# WS2818B.net
KiCad netlist of a schematic drawn in Altium Designer
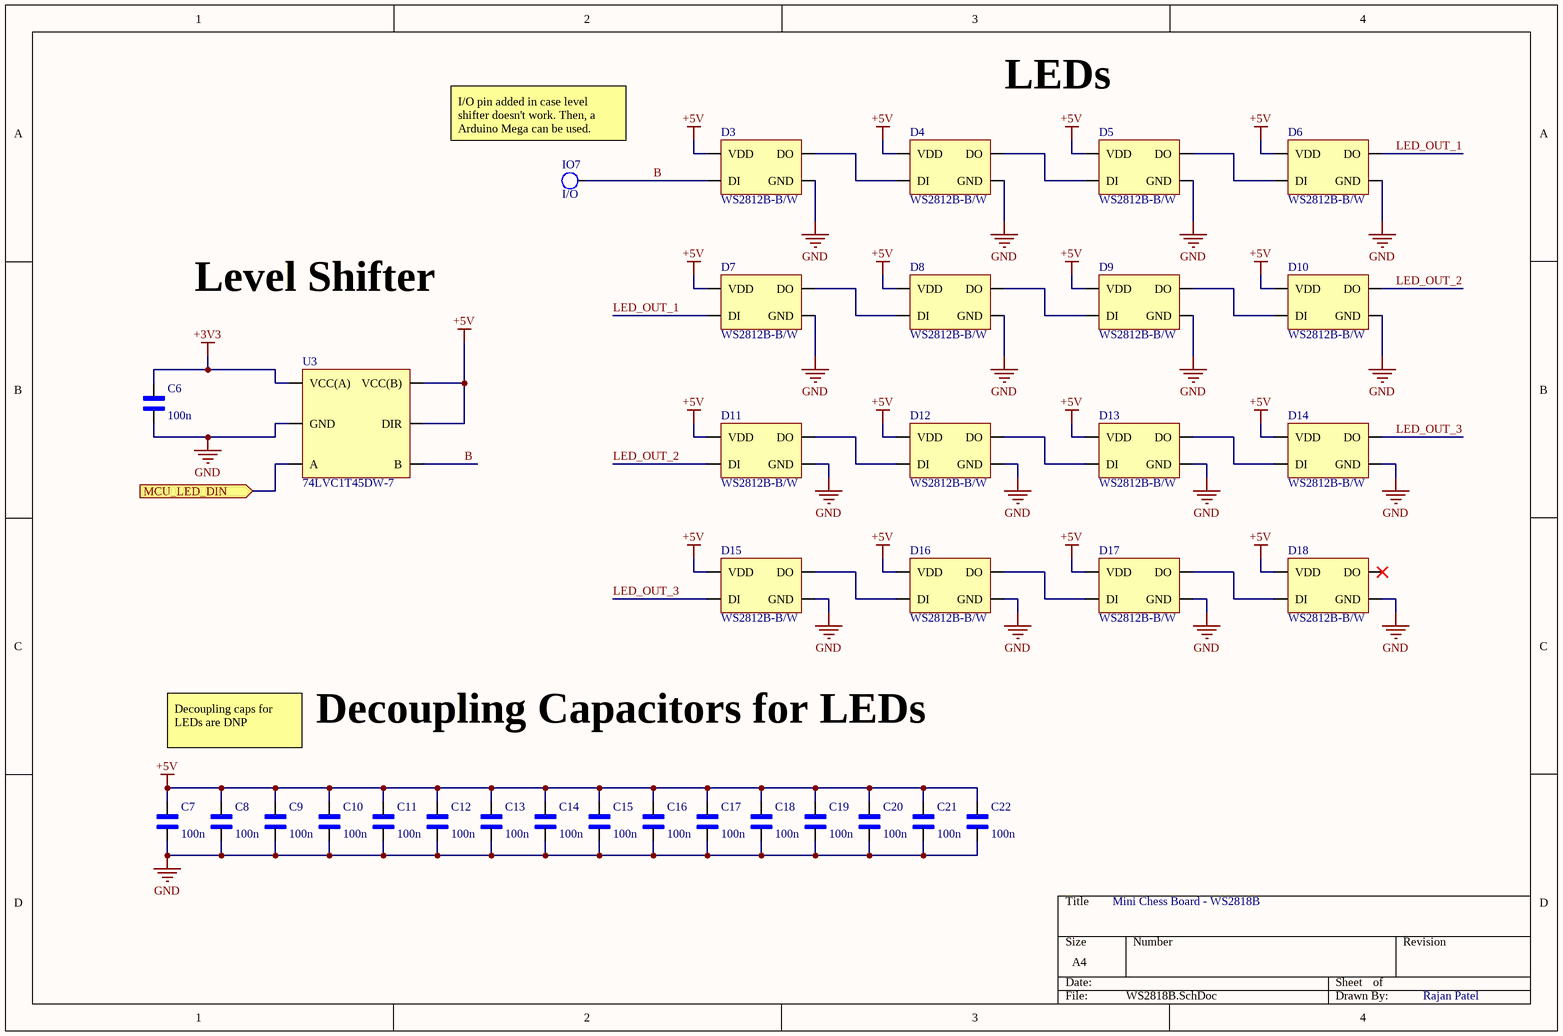
[diagram p0: WS2818B.SchDoc]

(export (version "E")
  (design (tool "Eeschema 10.0.6"))
  (components
    (comp (ref "C6")
      (value "100n")
      (footprint "CAP 0805")
      (libsource (lib "ChessBoardSchLib") (part "CAP 0805"))
    )
    (comp (ref "C7")
      (value "100n")
      (footprint "CAP 0805")
      (libsource (lib "ChessBoardSchLib") (part "CAP 0805"))
    )
    (comp (ref "C8")
      (value "100n")
      (footprint "CAP 0805")
      (libsource (lib "ChessBoardSchLib") (part "CAP 0805"))
    )
    (comp (ref "C9")
      (value "100n")
      (footprint "CAP 0805")
      (libsource (lib "ChessBoardSchLib") (part "CAP 0805"))
    )
    (comp (ref "C10")
      (value "100n")
      (footprint "CAP 0805")
      (libsource (lib "ChessBoardSchLib") (part "CAP 0805"))
    )
    (comp (ref "C11")
      (value "100n")
      (footprint "CAP 0805")
      (libsource (lib "ChessBoardSchLib") (part "CAP 0805"))
    )
    (comp (ref "C12")
      (value "100n")
      (footprint "CAP 0805")
      (libsource (lib "ChessBoardSchLib") (part "CAP 0805"))
    )
    (comp (ref "C13")
      (value "100n")
      (footprint "CAP 0805")
      (libsource (lib "ChessBoardSchLib") (part "CAP 0805"))
    )
    (comp (ref "C14")
      (value "100n")
      (footprint "CAP 0805")
      (libsource (lib "ChessBoardSchLib") (part "CAP 0805"))
    )
    (comp (ref "C15")
      (value "100n")
      (footprint "CAP 0805")
      (libsource (lib "ChessBoardSchLib") (part "CAP 0805"))
    )
    (comp (ref "C16")
      (value "100n")
      (footprint "CAP 0805")
      (libsource (lib "ChessBoardSchLib") (part "CAP 0805"))
    )
    (comp (ref "C17")
      (value "100n")
      (footprint "CAP 0805")
      (libsource (lib "ChessBoardSchLib") (part "CAP 0805"))
    )
    (comp (ref "C18")
      (value "100n")
      (footprint "CAP 0805")
      (libsource (lib "ChessBoardSchLib") (part "CAP 0805"))
    )
    (comp (ref "C19")
      (value "100n")
      (footprint "CAP 0805")
      (libsource (lib "ChessBoardSchLib") (part "CAP 0805"))
    )
    (comp (ref "C20")
      (value "100n")
      (footprint "CAP 0805")
      (libsource (lib "ChessBoardSchLib") (part "CAP 0805"))
    )
    (comp (ref "C21")
      (value "100n")
      (footprint "CAP 0805")
      (libsource (lib "ChessBoardSchLib") (part "CAP 0805"))
    )
    (comp (ref "C22")
      (value "100n")
      (footprint "CAP 0805")
      (libsource (lib "ChessBoardSchLib") (part "CAP 0805"))
    )
    (comp (ref "D3")
      (value "WS2812B-B/W")
      (footprint "WS2812B-B/W")
      (description "SMD5050 RGB LEDs(Built-in IC) ROHS")
      (fields (field (name "MANUFACTURER") "Worldsemi"))
      (libsource (lib "ChessBoardSchLib") (part "WS2812B-B/W"))
    )
    (comp (ref "D4")
      (value "WS2812B-B/W")
      (footprint "WS2812B-B/W")
      (description "SMD5050 RGB LEDs(Built-in IC) ROHS")
      (fields (field (name "MANUFACTURER") "Worldsemi"))
      (libsource (lib "ChessBoardSchLib") (part "WS2812B-B/W"))
    )
    (comp (ref "D5")
      (value "WS2812B-B/W")
      (footprint "WS2812B-B/W")
      (description "SMD5050 RGB LEDs(Built-in IC) ROHS")
      (fields (field (name "MANUFACTURER") "Worldsemi"))
      (libsource (lib "ChessBoardSchLib") (part "WS2812B-B/W"))
    )
    (comp (ref "D6")
      (value "WS2812B-B/W")
      (footprint "WS2812B-B/W")
      (description "SMD5050 RGB LEDs(Built-in IC) ROHS")
      (fields (field (name "MANUFACTURER") "Worldsemi"))
      (libsource (lib "ChessBoardSchLib") (part "WS2812B-B/W"))
    )
    (comp (ref "D7")
      (value "WS2812B-B/W")
      (footprint "WS2812B-B/W")
      (description "SMD5050 RGB LEDs(Built-in IC) ROHS")
      (fields (field (name "MANUFACTURER") "Worldsemi"))
      (libsource (lib "ChessBoardSchLib") (part "WS2812B-B/W"))
    )
    (comp (ref "D8")
      (value "WS2812B-B/W")
      (footprint "WS2812B-B/W")
      (description "SMD5050 RGB LEDs(Built-in IC) ROHS")
      (fields (field (name "MANUFACTURER") "Worldsemi"))
      (libsource (lib "ChessBoardSchLib") (part "WS2812B-B/W"))
    )
    (comp (ref "D9")
      (value "WS2812B-B/W")
      (footprint "WS2812B-B/W")
      (description "SMD5050 RGB LEDs(Built-in IC) ROHS")
      (fields (field (name "MANUFACTURER") "Worldsemi"))
      (libsource (lib "ChessBoardSchLib") (part "WS2812B-B/W"))
    )
    (comp (ref "D10")
      (value "WS2812B-B/W")
      (footprint "WS2812B-B/W")
      (description "SMD5050 RGB LEDs(Built-in IC) ROHS")
      (fields (field (name "MANUFACTURER") "Worldsemi"))
      (libsource (lib "ChessBoardSchLib") (part "WS2812B-B/W"))
    )
    (comp (ref "D11")
      (value "WS2812B-B/W")
      (footprint "WS2812B-B/W")
      (description "SMD5050 RGB LEDs(Built-in IC) ROHS")
      (fields (field (name "MANUFACTURER") "Worldsemi"))
      (libsource (lib "ChessBoardSchLib") (part "WS2812B-B/W"))
    )
    (comp (ref "D12")
      (value "WS2812B-B/W")
      (footprint "WS2812B-B/W")
      (description "SMD5050 RGB LEDs(Built-in IC) ROHS")
      (fields (field (name "MANUFACTURER") "Worldsemi"))
      (libsource (lib "ChessBoardSchLib") (part "WS2812B-B/W"))
    )
    (comp (ref "D13")
      (value "WS2812B-B/W")
      (footprint "WS2812B-B/W")
      (description "SMD5050 RGB LEDs(Built-in IC) ROHS")
      (fields (field (name "MANUFACTURER") "Worldsemi"))
      (libsource (lib "ChessBoardSchLib") (part "WS2812B-B/W"))
    )
    (comp (ref "D14")
      (value "WS2812B-B/W")
      (footprint "WS2812B-B/W")
      (description "SMD5050 RGB LEDs(Built-in IC) ROHS")
      (fields (field (name "MANUFACTURER") "Worldsemi"))
      (libsource (lib "ChessBoardSchLib") (part "WS2812B-B/W"))
    )
    (comp (ref "D15")
      (value "WS2812B-B/W")
      (footprint "WS2812B-B/W")
      (description "SMD5050 RGB LEDs(Built-in IC) ROHS")
      (fields (field (name "MANUFACTURER") "Worldsemi"))
      (libsource (lib "ChessBoardSchLib") (part "WS2812B-B/W"))
    )
    (comp (ref "D16")
      (value "WS2812B-B/W")
      (footprint "WS2812B-B/W")
      (description "SMD5050 RGB LEDs(Built-in IC) ROHS")
      (fields (field (name "MANUFACTURER") "Worldsemi"))
      (libsource (lib "ChessBoardSchLib") (part "WS2812B-B/W"))
    )
    (comp (ref "D17")
      (value "WS2812B-B/W")
      (footprint "WS2812B-B/W")
      (description "SMD5050 RGB LEDs(Built-in IC) ROHS")
      (fields (field (name "MANUFACTURER") "Worldsemi"))
      (libsource (lib "ChessBoardSchLib") (part "WS2812B-B/W"))
    )
    (comp (ref "D18")
      (value "WS2812B-B/W")
      (footprint "WS2812B-B/W")
      (description "SMD5050 RGB LEDs(Built-in IC) ROHS")
      (fields (field (name "MANUFACTURER") "Worldsemi"))
      (libsource (lib "ChessBoardSchLib") (part "WS2812B-B/W"))
    )
    (comp (ref "IO7") (value "I/O") (footprint "I/O") (libsource (lib "MiniChessBoardSchLib") (part "I/O")))
    (comp (ref "U3")
      (value "74LVC1T45DW-7")
      (footprint "74LVC1T45DW-7")
      (description "Bus Transceiver, LVC/LCX/Z Series, 1-Func, 1-Bit, True Output, CMOS, PDSO6")
      (fields (field (name "MANUFACTURER") "Diodes"))
      (libsource (lib "ChessBoardSchLib") (part "74LVC1T45DW-7"))
    )
  )
  (nets
    (net (code "1") (name "+3V3") (class "Default")
      (node (ref "C6") (pin "2") (pinfunction "2_2") (pintype "passive"))
      (node (ref "U3") (pin "1") (pinfunction "VCC(A)_1") (pintype "passive"))
    )
    (net (code "2") (name "+5V") (class "Default")
      (node (ref "C10") (pin "2") (pinfunction "2_2") (pintype "passive"))
      (node (ref "C11") (pin "2") (pinfunction "2_2") (pintype "passive"))
      (node (ref "C12") (pin "2") (pinfunction "2_2") (pintype "passive"))
      (node (ref "C13") (pin "2") (pinfunction "2_2") (pintype "passive"))
      (node (ref "C14") (pin "2") (pinfunction "2_2") (pintype "passive"))
      (node (ref "C15") (pin "2") (pinfunction "2_2") (pintype "passive"))
      (node (ref "C16") (pin "2") (pinfunction "2_2") (pintype "passive"))
      (node (ref "C17") (pin "2") (pinfunction "2_2") (pintype "passive"))
      (node (ref "C18") (pin "2") (pinfunction "2_2") (pintype "passive"))
      (node (ref "C19") (pin "2") (pinfunction "2_2") (pintype "passive"))
      (node (ref "C20") (pin "2") (pinfunction "2_2") (pintype "passive"))
      (node (ref "C21") (pin "2") (pinfunction "2_2") (pintype "passive"))
      (node (ref "C22") (pin "2") (pinfunction "2_2") (pintype "passive"))
      (node (ref "C7") (pin "2") (pinfunction "2_2") (pintype "passive"))
      (node (ref "C8") (pin "2") (pinfunction "2_2") (pintype "passive"))
      (node (ref "C9") (pin "2") (pinfunction "2_2") (pintype "passive"))
      (node (ref "D10") (pin "1") (pinfunction "VDD_1") (pintype "passive"))
      (node (ref "D11") (pin "1") (pinfunction "VDD_1") (pintype "passive"))
      (node (ref "D12") (pin "1") (pinfunction "VDD_1") (pintype "passive"))
      (node (ref "D13") (pin "1") (pinfunction "VDD_1") (pintype "passive"))
      (node (ref "D14") (pin "1") (pinfunction "VDD_1") (pintype "passive"))
      (node (ref "D15") (pin "1") (pinfunction "VDD_1") (pintype "passive"))
      (node (ref "D16") (pin "1") (pinfunction "VDD_1") (pintype "passive"))
      (node (ref "D17") (pin "1") (pinfunction "VDD_1") (pintype "passive"))
      (node (ref "D18") (pin "1") (pinfunction "VDD_1") (pintype "passive"))
      (node (ref "D3") (pin "1") (pinfunction "VDD_1") (pintype "passive"))
      (node (ref "D4") (pin "1") (pinfunction "VDD_1") (pintype "passive"))
      (node (ref "D5") (pin "1") (pinfunction "VDD_1") (pintype "passive"))
      (node (ref "D6") (pin "1") (pinfunction "VDD_1") (pintype "passive"))
      (node (ref "D7") (pin "1") (pinfunction "VDD_1") (pintype "passive"))
      (node (ref "D8") (pin "1") (pinfunction "VDD_1") (pintype "passive"))
      (node (ref "D9") (pin "1") (pinfunction "VDD_1") (pintype "passive"))
      (node (ref "U3") (pin "5") (pinfunction "DIR_5") (pintype "passive"))
      (node (ref "U3") (pin "6") (pinfunction "VCC(B)_6") (pintype "passive"))
    )
    (net (code "3") (name "/B") (class "Default")
      (node (ref "D3") (pin "2") (pinfunction "DI_2") (pintype "passive"))
      (node (ref "IO7") (pin "1") (pinfunction "1_1") (pintype "passive"))
      (node (ref "U3") (pin "4") (pinfunction "B_4") (pintype "passive"))
    )
    (net (code "4") (name "/LED_OUT_1") (class "Default")
      (node (ref "D6") (pin "3") (pinfunction "DO_3") (pintype "passive"))
      (node (ref "D7") (pin "2") (pinfunction "DI_2") (pintype "passive"))
    )
    (net (code "5") (name "/LED_OUT_2") (class "Default")
      (node (ref "D10") (pin "3") (pinfunction "DO_3") (pintype "passive"))
      (node (ref "D11") (pin "2") (pinfunction "DI_2") (pintype "passive"))
    )
    (net (code "6") (name "/LED_OUT_3") (class "Default")
      (node (ref "D14") (pin "3") (pinfunction "DO_3") (pintype "passive"))
      (node (ref "D15") (pin "2") (pinfunction "DI_2") (pintype "passive"))
    )
    (net (code "7") (name "/MCU_LED_DIN") (class "Default")
      (node (ref "U3") (pin "3") (pinfunction "A_3") (pintype "passive"))
    )
    (net (code "8") (name "GND") (class "Default")
      (node (ref "C10") (pin "1") (pinfunction "1_1") (pintype "passive"))
      (node (ref "C11") (pin "1") (pinfunction "1_1") (pintype "passive"))
      (node (ref "C12") (pin "1") (pinfunction "1_1") (pintype "passive"))
      (node (ref "C13") (pin "1") (pinfunction "1_1") (pintype "passive"))
      (node (ref "C14") (pin "1") (pinfunction "1_1") (pintype "passive"))
      (node (ref "C15") (pin "1") (pinfunction "1_1") (pintype "passive"))
      (node (ref "C16") (pin "1") (pinfunction "1_1") (pintype "passive"))
      (node (ref "C17") (pin "1") (pinfunction "1_1") (pintype "passive"))
      (node (ref "C18") (pin "1") (pinfunction "1_1") (pintype "passive"))
      (node (ref "C19") (pin "1") (pinfunction "1_1") (pintype "passive"))
      (node (ref "C20") (pin "1") (pinfunction "1_1") (pintype "passive"))
      (node (ref "C21") (pin "1") (pinfunction "1_1") (pintype "passive"))
      (node (ref "C22") (pin "1") (pinfunction "1_1") (pintype "passive"))
      (node (ref "C6") (pin "1") (pinfunction "1_1") (pintype "passive"))
      (node (ref "C7") (pin "1") (pinfunction "1_1") (pintype "passive"))
      (node (ref "C8") (pin "1") (pinfunction "1_1") (pintype "passive"))
      (node (ref "C9") (pin "1") (pinfunction "1_1") (pintype "passive"))
      (node (ref "D10") (pin "4") (pinfunction "GND_4") (pintype "passive"))
      (node (ref "D11") (pin "4") (pinfunction "GND_4") (pintype "passive"))
      (node (ref "D12") (pin "4") (pinfunction "GND_4") (pintype "passive"))
      (node (ref "D13") (pin "4") (pinfunction "GND_4") (pintype "passive"))
      (node (ref "D14") (pin "4") (pinfunction "GND_4") (pintype "passive"))
      (node (ref "D15") (pin "4") (pinfunction "GND_4") (pintype "passive"))
      (node (ref "D16") (pin "4") (pinfunction "GND_4") (pintype "passive"))
      (node (ref "D17") (pin "4") (pinfunction "GND_4") (pintype "passive"))
      (node (ref "D18") (pin "4") (pinfunction "GND_4") (pintype "passive"))
      (node (ref "D3") (pin "4") (pinfunction "GND_4") (pintype "passive"))
      (node (ref "D4") (pin "4") (pinfunction "GND_4") (pintype "passive"))
      (node (ref "D5") (pin "4") (pinfunction "GND_4") (pintype "passive"))
      (node (ref "D6") (pin "4") (pinfunction "GND_4") (pintype "passive"))
      (node (ref "D7") (pin "4") (pinfunction "GND_4") (pintype "passive"))
      (node (ref "D8") (pin "4") (pinfunction "GND_4") (pintype "passive"))
      (node (ref "D9") (pin "4") (pinfunction "GND_4") (pintype "passive"))
      (node (ref "U3") (pin "2") (pinfunction "GND_2") (pintype "passive"))
    )
    (net (code "9") (name "Net-(D3-DO)") (class "Default")
      (node (ref "D3") (pin "3") (pinfunction "DO_3") (pintype "passive"))
      (node (ref "D4") (pin "2") (pinfunction "DI_2") (pintype "passive"))
    )
    (net (code "10") (name "Net-(D4-DO)") (class "Default")
      (node (ref "D4") (pin "3") (pinfunction "DO_3") (pintype "passive"))
      (node (ref "D5") (pin "2") (pinfunction "DI_2") (pintype "passive"))
    )
    (net (code "11") (name "Net-(D5-DO)") (class "Default")
      (node (ref "D5") (pin "3") (pinfunction "DO_3") (pintype "passive"))
      (node (ref "D6") (pin "2") (pinfunction "DI_2") (pintype "passive"))
    )
    (net (code "12") (name "Net-(D7-DO)") (class "Default")
      (node (ref "D7") (pin "3") (pinfunction "DO_3") (pintype "passive"))
      (node (ref "D8") (pin "2") (pinfunction "DI_2") (pintype "passive"))
    )
    (net (code "13") (name "Net-(D8-DO)") (class "Default")
      (node (ref "D8") (pin "3") (pinfunction "DO_3") (pintype "passive"))
      (node (ref "D9") (pin "2") (pinfunction "DI_2") (pintype "passive"))
    )
    (net (code "14") (name "Net-(D10-DI)") (class "Default")
      (node (ref "D10") (pin "2") (pinfunction "DI_2") (pintype "passive"))
      (node (ref "D9") (pin "3") (pinfunction "DO_3") (pintype "passive"))
    )
    (net (code "15") (name "Net-(D11-DO)") (class "Default")
      (node (ref "D11") (pin "3") (pinfunction "DO_3") (pintype "passive"))
      (node (ref "D12") (pin "2") (pinfunction "DI_2") (pintype "passive"))
    )
    (net (code "16") (name "Net-(D12-DO)") (class "Default")
      (node (ref "D12") (pin "3") (pinfunction "DO_3") (pintype "passive"))
      (node (ref "D13") (pin "2") (pinfunction "DI_2") (pintype "passive"))
    )
    (net (code "17") (name "Net-(D13-DO)") (class "Default")
      (node (ref "D13") (pin "3") (pinfunction "DO_3") (pintype "passive"))
      (node (ref "D14") (pin "2") (pinfunction "DI_2") (pintype "passive"))
    )
    (net (code "18") (name "Net-(D15-DO)") (class "Default")
      (node (ref "D15") (pin "3") (pinfunction "DO_3") (pintype "passive"))
      (node (ref "D16") (pin "2") (pinfunction "DI_2") (pintype "passive"))
    )
    (net (code "19") (name "Net-(D16-DO)") (class "Default")
      (node (ref "D16") (pin "3") (pinfunction "DO_3") (pintype "passive"))
      (node (ref "D17") (pin "2") (pinfunction "DI_2") (pintype "passive"))
    )
    (net (code "20") (name "Net-(D17-DO)") (class "Default")
      (node (ref "D17") (pin "3") (pinfunction "DO_3") (pintype "passive"))
      (node (ref "D18") (pin "2") (pinfunction "DI_2") (pintype "passive"))
    )
    (net (code "21") (name "unconnected-(D18-DO-Pad3)") (class "Default")
      (node (ref "D18") (pin "3") (pinfunction "DO_3") (pintype "passive+no_connect"))
    )
  )
)
